# PowerSwitch.net
KiCad netlist of a schematic drawn in Altium Designer
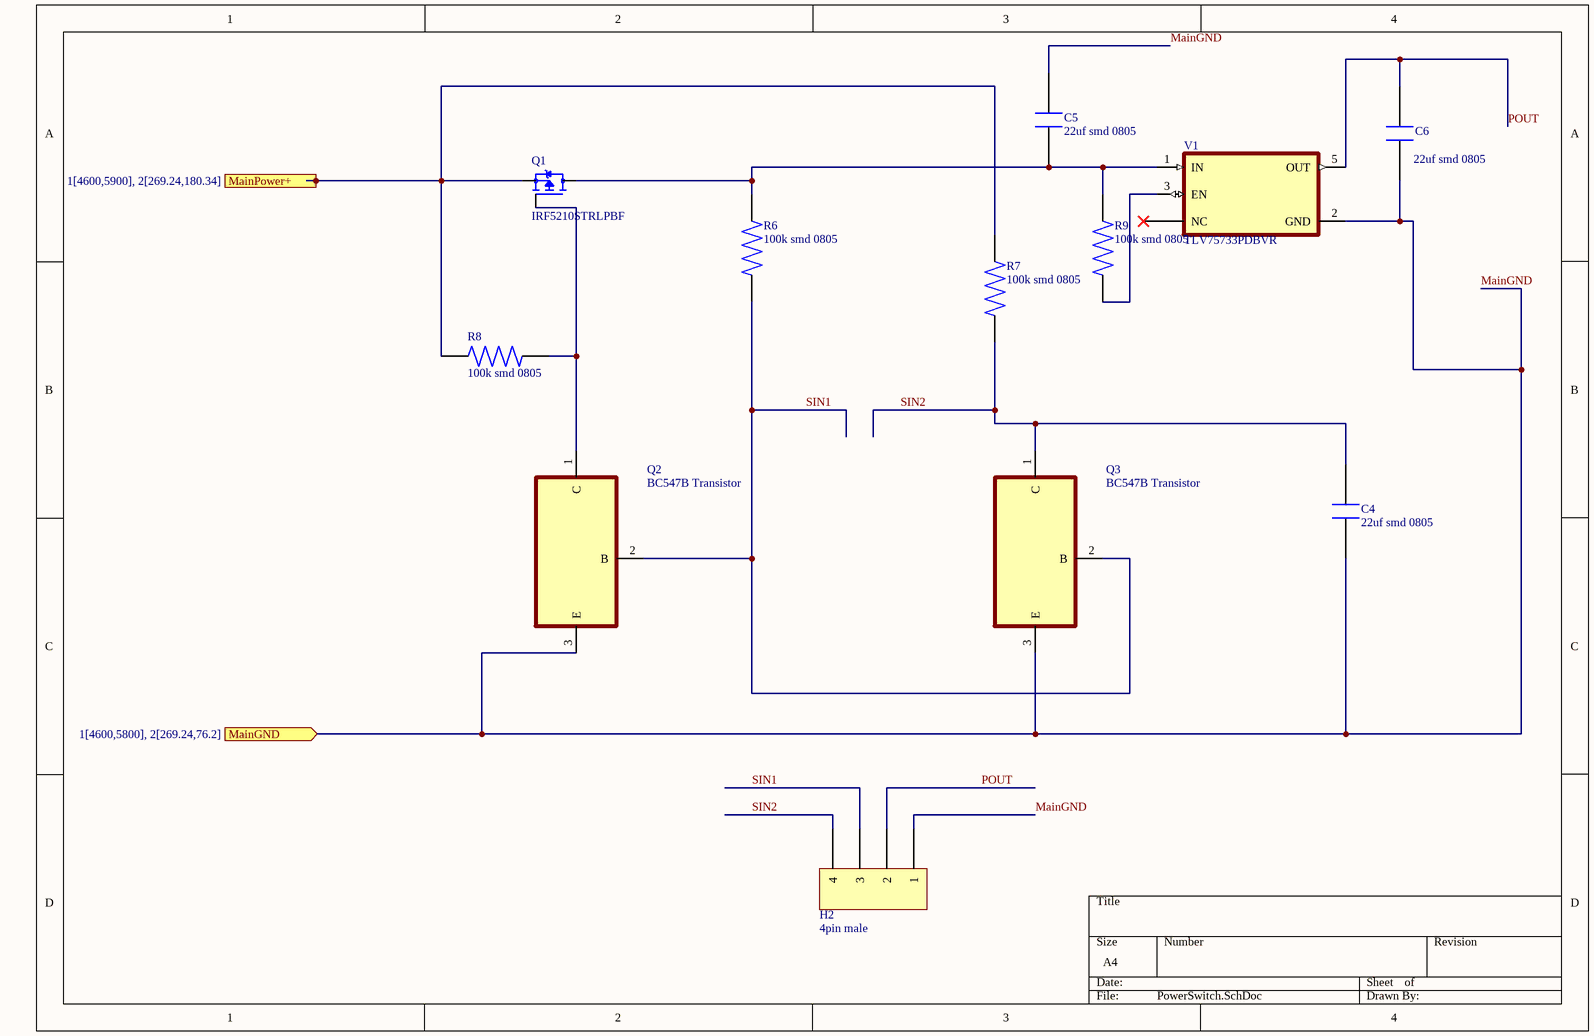
[diagram p0: PowerSwitch.SchDoc]

(export (version "E")
  (design (tool "Eeschema 10.0.6"))
  (components
    (comp (ref "C4")
      (value "22uf smd 0805")
      (footprint "0805 SMD")
      (fields
        (field (name "MANUFACTURER") "Samsung")
        (field (name "MANUFACTURER PART NUMBER") "CL21A226KQCLRNC")
      )
      (libsource (lib "Project") (part "CL21A226KQCLRNC"))
    )
    (comp (ref "C5")
      (value "22uf smd 0805")
      (footprint "0805 SMD")
      (fields
        (field (name "MANUFACTURER") "Samsung")
        (field (name "MANUFACTURER PART NUMBER") "CL21A226KQCLRNC")
      )
      (libsource (lib "Project") (part "CL21A226KQCLRNC"))
    )
    (comp (ref "C6")
      (value "22uf smd 0805")
      (footprint "0805 SMD")
      (fields
        (field (name "MANUFACTURER") "Samsung")
        (field (name "MANUFACTURER PART NUMBER") "CL21A226KQCLRNC")
      )
      (libsource (lib "Project") (part "CL21A226KQCLRNC"))
    )
    (comp (ref "H2")
      (value "4pin male")
      (footprint "4pin Header Male")
      (description "Conn Unshrouded Header HDR 4 POS 2.54mm Solder RA Thru-Hole Poly Bag")
      (fields
        (field (name "MANUFACTURER") "Amphenol ICC / FCI")
        (field (name "MANUFACTURER PART NUMBER") "10129379-904002BLF")
      )
      (libsource (lib "Project") (part "10129379-904002BLF"))
    )
    (comp (ref "Q1")
      (value "IRF5210STRLPBF")
      (footprint "TO254P1041X444X1930-3")
      (fields (field (name "MANUFACTURER") "Infineon"))
      (libsource (lib "Project") (part "IRF5210STRLPBF"))
    )
    (comp (ref "Q2")
      (value "BC547B Transistor")
      (footprint "TO127P254X732-3")
      (description "Small Signal Bipolar Transistor, 0.1A I(C), 45V V(BR)CEO, 1-Element, NPN, Silicon, TO-92")
      (fields
        (field (name "MANUFACTURER") "ON Semiconductor / Fairchild")
        (field (name "MANUFACTURER PART NUMBER") "BC547B")
      )
      (libsource (lib "Project") (part "BC547B"))
    )
    (comp (ref "Q3")
      (value "BC547B Transistor")
      (footprint "TO127P254X732-3")
      (description "Small Signal Bipolar Transistor, 0.1A I(C), 45V V(BR)CEO, 1-Element, NPN, Silicon, TO-92")
      (fields
        (field (name "MANUFACTURER") "ON Semiconductor / Fairchild")
        (field (name "MANUFACTURER PART NUMBER") "BC547B")
      )
      (libsource (lib "Project") (part "BC547B"))
    )
    (comp (ref "R6")
      (value "100k smd 0805")
      (footprint "0805 SMD")
      (fields
        (field (name "MANUFACTURER") "Yageo")
        (field (name "MANUFACTURER PART NUMBER") "RC0805FR-07100KL")
        (field (name "TOLERANCE") "1%")
      )
      (libsource (lib "Project") (part "RC0805FR-07100KL"))
    )
    (comp (ref "R7")
      (value "100k smd 0805")
      (footprint "0805 SMD")
      (fields
        (field (name "MANUFACTURER") "Yageo")
        (field (name "MANUFACTURER PART NUMBER") "RC0805FR-07100KL")
        (field (name "TOLERANCE") "1%")
      )
      (libsource (lib "Project") (part "RC0805FR-07100KL"))
    )
    (comp (ref "R8")
      (value "100k smd 0805")
      (footprint "0805 SMD")
      (fields
        (field (name "MANUFACTURER") "Yageo")
        (field (name "MANUFACTURER PART NUMBER") "RC0805FR-07100KL")
        (field (name "TOLERANCE") "1%")
      )
      (libsource (lib "Project") (part "RC0805FR-07100KL"))
    )
    (comp (ref "R9")
      (value "100k smd 0805")
      (footprint "0805 SMD")
      (fields
        (field (name "MANUFACTURER") "Yageo")
        (field (name "MANUFACTURER PART NUMBER") "RC0805FR-07100KL")
        (field (name "TOLERANCE") "1%")
      )
      (libsource (lib "Project") (part "RC0805FR-07100KL"))
    )
    (comp (ref "V1")
      (value "TLV75733PDBVR")
      (footprint "SOT95P280X145-5N")
      (description "Fixed Positive LDO Regulator, 3.3V, 0.475V Dropout, PDSO5")
      (fields (field (name "MANUFACTURER") "Texas Instruments"))
      (libsource (lib "Project") (part "TLV75733PDBVR"))
    )
  )
  (nets
    (net (code "1") (name "/MainGND") (class "Default")
      (node (ref "C4") (pin "1") (pinfunction "4_1") (pintype "passive"))
      (node (ref "C5") (pin "2") (pinfunction "5_2") (pintype "passive"))
      (node (ref "C6") (pin "1") (pinfunction "4_1") (pintype "passive"))
      (node (ref "H2") (pin "1") (pinfunction "1_1") (pintype "passive"))
      (node (ref "Q2") (pin "3") (pinfunction "E_3") (pintype "passive"))
      (node (ref "Q3") (pin "3") (pinfunction "E_3") (pintype "passive"))
      (node (ref "V1") (pin "2") (pinfunction "GND_2") (pintype "power_in"))
    )
    (net (code "2") (name "/MainPower+") (class "Default")
      (node (ref "Q1") (pin "2") (pinfunction "S_2") (pintype "passive"))
      (node (ref "R7") (pin "2") (pinfunction "2_2") (pintype "passive"))
      (node (ref "R8") (pin "1") (pinfunction "1_1") (pintype "passive"))
    )
    (net (code "3") (name "/POUT") (class "Default")
      (node (ref "C6") (pin "2") (pinfunction "5_2") (pintype "passive"))
      (node (ref "H2") (pin "2") (pinfunction "2_2") (pintype "passive"))
      (node (ref "V1") (pin "5") (pinfunction "OUT_5") (pintype "output"))
    )
    (net (code "4") (name "/SIN1") (class "Default")
      (node (ref "H2") (pin "3") (pinfunction "3_3") (pintype "passive"))
      (node (ref "Q2") (pin "2") (pinfunction "B_2") (pintype "passive"))
      (node (ref "Q3") (pin "2") (pinfunction "B_2") (pintype "passive"))
      (node (ref "R6") (pin "1") (pinfunction "1_1") (pintype "passive"))
    )
    (net (code "5") (name "/SIN2") (class "Default")
      (node (ref "C4") (pin "2") (pinfunction "5_2") (pintype "passive"))
      (node (ref "H2") (pin "4") (pinfunction "4_4") (pintype "passive"))
      (node (ref "Q3") (pin "1") (pinfunction "C_1") (pintype "passive"))
      (node (ref "R7") (pin "1") (pinfunction "1_1") (pintype "passive"))
    )
    (net (code "6") (name "Net-(C5-4)") (class "Default")
      (node (ref "C5") (pin "1") (pinfunction "4_1") (pintype "passive"))
      (node (ref "Q1") (pin "3") (pinfunction "D_3") (pintype "passive"))
      (node (ref "R6") (pin "2") (pinfunction "2_2") (pintype "passive"))
      (node (ref "R9") (pin "1") (pinfunction "1_1") (pintype "passive"))
      (node (ref "V1") (pin "1") (pinfunction "IN_1") (pintype "input"))
    )
    (net (code "7") (name "Net-(Q1-G)") (class "Default")
      (node (ref "Q1") (pin "1") (pinfunction "G_1") (pintype "passive"))
      (node (ref "Q2") (pin "1") (pinfunction "C_1") (pintype "passive"))
      (node (ref "R8") (pin "2") (pinfunction "2_2") (pintype "passive"))
    )
    (net (code "8") (name "Net-(V1-EN)") (class "Default")
      (node (ref "R9") (pin "2") (pinfunction "2_2") (pintype "passive"))
      (node (ref "V1") (pin "3") (pinfunction "EN_3") (pintype "bidirectional"))
    )
    (net (code "9") (name "unconnected-(V1-NC-Pad4)") (class "Default")
      (node (ref "V1") (pin "4") (pinfunction "NC_4") (pintype "passive+no_connect"))
    )
  )
)
